# DAC.net
KiCad netlist of a schematic drawn in Altium Designer
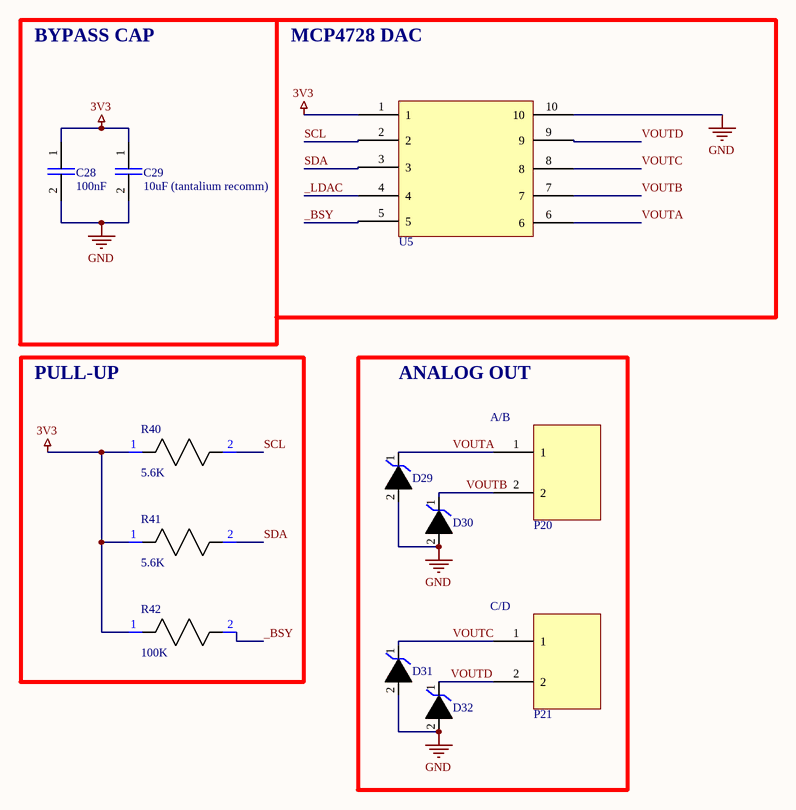
[diagram p0: DAC.SchDoc]

(export (version "E")
  (design (tool "Eeschema 10.0.6"))
  (components
    (comp (ref "C28")
      (value "100nF")
      (footprint "0603 Cap")
      (description "SMD 0603 (ceramic) capacitor")
      (fields
        (field (name "MANUFACTURER") "Murata")
        (field (name "MANUFACTURER PART NUMBER") "GRM21BR71C225KA12L")
      )
      (libsource (lib "Lib") (part "0603 Cap"))
    )
    (comp (ref "C29")
      (value "10uF (tantalium recomm)")
      (footprint "0603 Cap")
      (description "SMD 0603 (ceramic) capacitor")
      (fields
        (field (name "MANUFACTURER") "Murata")
        (field (name "MANUFACTURER PART NUMBER") "GRM21BR71C225KA12L")
      )
      (libsource (lib "Lib") (part "0603 Cap"))
    )
    (comp (ref "D29")
      (value "TVS")
      (footprint "TVS DIODE")
      (description "Schematic for TVS diode")
      (libsource (lib "Lib") (part "TVS Diode"))
    )
    (comp (ref "D30")
      (value "TVS")
      (footprint "TVS DIODE")
      (description "Schematic for TVS diode")
      (libsource (lib "Lib") (part "TVS Diode"))
    )
    (comp (ref "D31")
      (value "TVS")
      (footprint "TVS DIODE")
      (description "Schematic for TVS diode")
      (libsource (lib "Lib") (part "TVS Diode"))
    )
    (comp (ref "D32")
      (value "TVS")
      (footprint "TVS DIODE")
      (description "Schematic for TVS diode")
      (libsource (lib "Lib") (part "TVS Diode"))
    )
    (comp (ref "P20")
      (value "A/B")
      (footprint "WR-TBL 322 2H")
      (description "322 series 2 pin header")
      (libsource (lib "Lib") (part "322-2H"))
    )
    (comp (ref "P21")
      (value "C/D")
      (footprint "WR-TBL 322 2H")
      (description "322 series 2 pin header")
      (libsource (lib "Lib") (part "322-2H"))
    )
    (comp (ref "R40")
      (value "5.6K")
      (footprint "0603 RES")
      (description "Can be used for SMD resistors")
      (fields (field (name "Comment") "Resistor"))
      (libsource (lib "Lib") (part "0603 Res"))
    )
    (comp (ref "R41")
      (value "5.6K")
      (footprint "0603 RES")
      (description "Can be used for SMD resistors")
      (fields (field (name "Comment") "Resistor"))
      (libsource (lib "Lib") (part "0603 Res"))
    )
    (comp (ref "R42")
      (value "100K")
      (footprint "0603 RES")
      (description "Can be used for SMD resistors")
      (fields (field (name "Comment") "Resistor"))
      (libsource (lib "Lib") (part "0603 Res"))
    )
    (comp (ref "U5") (value "MCP4728") (footprint "10-PIN MSOP") (libsource (lib "Lib") (part "10-PIN MSOP")))
  )
  (nets
    (net (code "1") (name "/SCL") (class "Default")
      (node (ref "R40") (pin "2") (pinfunction "21_2") (pintype "passive"))
      (node (ref "U5") (pin "2") (pinfunction "2_2") (pintype "passive"))
    )
    (net (code "2") (name "/SDA") (class "Default")
      (node (ref "R41") (pin "2") (pinfunction "21_2") (pintype "passive"))
      (node (ref "U5") (pin "3") (pinfunction "3_3") (pintype "passive"))
    )
    (net (code "3") (name "/VOUTA") (class "Default")
      (node (ref "D29") (pin "1") (pinfunction "1_1") (pintype "passive"))
      (node (ref "P20") (pin "1") (pinfunction "1_1") (pintype "passive"))
      (node (ref "U5") (pin "6") (pinfunction "6_6") (pintype "passive"))
    )
    (net (code "4") (name "/VOUTB") (class "Default")
      (node (ref "D30") (pin "1") (pinfunction "1_1") (pintype "passive"))
      (node (ref "P20") (pin "2") (pinfunction "2_2") (pintype "passive"))
      (node (ref "U5") (pin "7") (pinfunction "7_7") (pintype "passive"))
    )
    (net (code "5") (name "/VOUTC") (class "Default")
      (node (ref "D31") (pin "1") (pinfunction "1_1") (pintype "passive"))
      (node (ref "P21") (pin "1") (pinfunction "1_1") (pintype "passive"))
      (node (ref "U5") (pin "8") (pinfunction "8_8") (pintype "passive"))
    )
    (net (code "6") (name "/VOUTD") (class "Default")
      (node (ref "D32") (pin "1") (pinfunction "1_1") (pintype "passive"))
      (node (ref "P21") (pin "2") (pinfunction "2_2") (pintype "passive"))
      (node (ref "U5") (pin "9") (pinfunction "9_9") (pintype "passive"))
    )
    (net (code "7") (name "/_BSY") (class "Default")
      (node (ref "R42") (pin "2") (pinfunction "21_2") (pintype "passive"))
      (node (ref "U5") (pin "5") (pinfunction "5_5") (pintype "passive"))
    )
    (net (code "8") (name "/_LDAC") (class "Default")
      (node (ref "U5") (pin "4") (pinfunction "4_4") (pintype "passive"))
    )
    (net (code "9") (name "3V3") (class "Default")
      (node (ref "C28") (pin "1") (pinfunction "11_1") (pintype "passive"))
      (node (ref "C29") (pin "1") (pinfunction "11_1") (pintype "passive"))
      (node (ref "R40") (pin "1") (pinfunction "22_1") (pintype "passive"))
      (node (ref "R41") (pin "1") (pinfunction "22_1") (pintype "passive"))
      (node (ref "R42") (pin "1") (pinfunction "22_1") (pintype "passive"))
      (node (ref "U5") (pin "1") (pinfunction "1_1") (pintype "passive"))
    )
    (net (code "10") (name "GND") (class "Default")
      (node (ref "C28") (pin "2") (pinfunction "12_2") (pintype "passive"))
      (node (ref "C29") (pin "2") (pinfunction "12_2") (pintype "passive"))
      (node (ref "D29") (pin "2") (pinfunction "2_2") (pintype "passive"))
      (node (ref "D30") (pin "2") (pinfunction "2_2") (pintype "passive"))
      (node (ref "D31") (pin "2") (pinfunction "2_2") (pintype "passive"))
      (node (ref "D32") (pin "2") (pinfunction "2_2") (pintype "passive"))
      (node (ref "U5") (pin "10") (pinfunction "10_10") (pintype "passive"))
    )
  )
)
